# Mechanical.net
KiCad netlist of a schematic drawn in Altium Designer
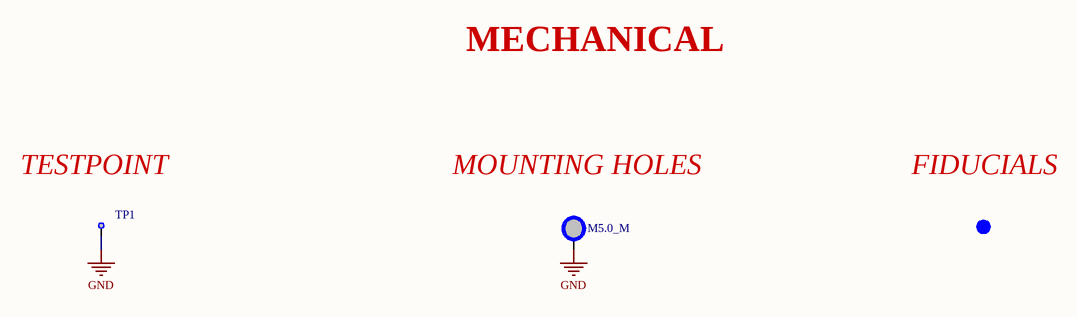
[diagram p0: Mechanical.SchDoc]

(export (version "E")
  (design (tool "Eeschema 10.0.6"))
  (components
    (comp (ref "Drill1") (value "M5.0_M") (footprint "M5.0_M") (libsource (lib "Drills") (part "Drill")))
    (comp (ref "FIID1")
      (value "Fiducial")
      (footprint "Fiducial")
      (libsource (lib "Drills") (part "Fiducial"))
    )
    (comp (ref "TP1")
      (value "Testpoint")
      (footprint "Testpoint")
      (libsource (lib "Drills") (part "Testpoint"))
    )
  )
  (nets
    (net (code "1") (name "GND") (class "Default")
      (node (ref "Drill1") (pin "1") (pinfunction "1_1") (pintype "passive"))
      (node (ref "TP1") (pin "1") (pinfunction "1_1") (pintype "passive"))
    )
  )
)
